# AnalogControlBoard.net
KiCad netlist of a schematic drawn in Altium Designer
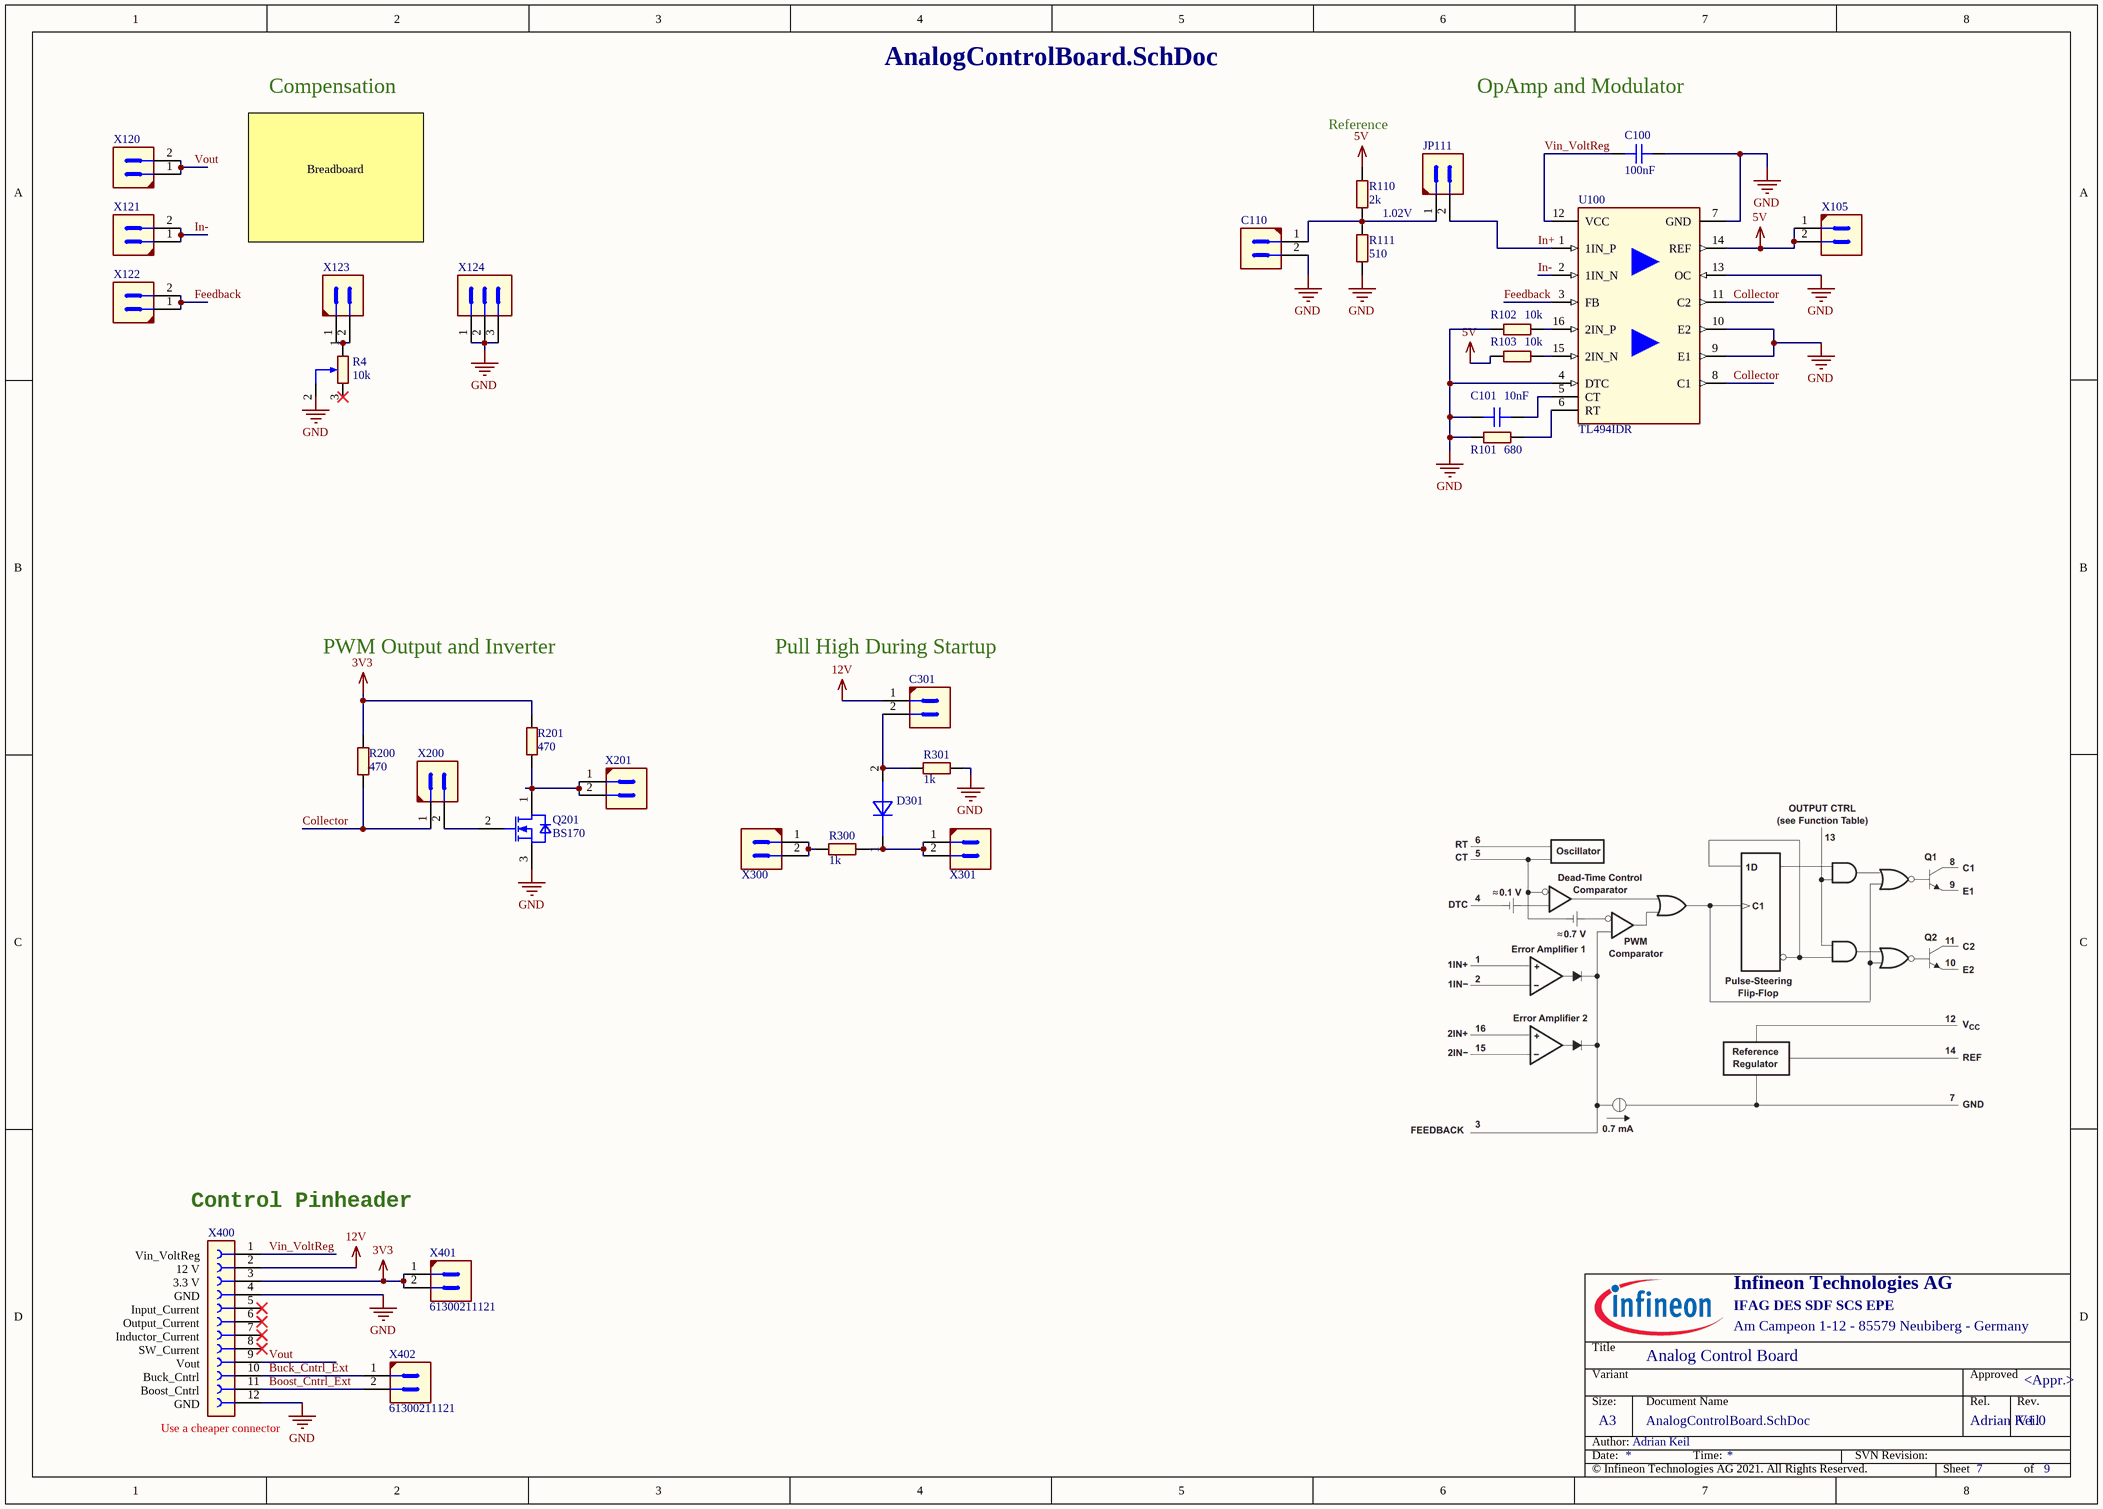
[diagram p0: AnalogControlBoard.SchDoc]

(export (version "E")
  (design (tool "Eeschema 10.0.6"))
  (components
    (comp (ref "C100")
      (value "100nF")
      (footprint "CAPRR254W51L508T318H736B")
      (fields (field (name "LEGACY PARTNUMBER") "CAP01010813") (field (name "MANUFACTURER") "Kemet"))
      (libsource (lib "PCBLibraryData") (part "CAP-SGL-STD-02P_00000001"))
    )
    (comp (ref "C101")
      (value "10nF")
      (footprint "CAPRR254W51L508T318H736B")
      (fields (field (name "LEGACY PARTNUMBER") "CAP01010813") (field (name "MANUFACTURER") "Kemet"))
      (libsource (lib "PCBLibraryData") (part "CAP-SGL-STD-02P_00000001"))
    )
    (comp (ref "C110")
      (value "61300211121")
      (footprint "CON-M-THT-61300211121")
      (description "Header, 2.54mm Pitch, 2 pin, Vertical, Single Row")
      (fields
        (field (name "LEGACY PARTNUMBER") "CON01500943")
        (field (name "MANUFACTURER") "Wurth Elektronik")
      )
      (libsource (lib "") (part "Header 2_3"))
    )
    (comp (ref "C301")
      (value "61300211121")
      (footprint "CON-M-THT-61300211121")
      (description "Header, 2.54mm Pitch, 2 pin, Vertical, Single Row")
      (fields
        (field (name "LEGACY PARTNUMBER") "CON01500943")
        (field (name "MANUFACTURER") "Wurth Elektronik")
      )
      (libsource (lib "") (part "Header 2_1"))
    )
    (comp (ref "D301")
      (value "1N4001-E3/54")
      (footprint "DIOAD1020W78L465D235B")
      (description "General Purpose Plastic Rectifier, 1.0A/50Vrrm")
      (fields (field (name "LEGACY PARTNUMBER") "DIO01300395") (field (name "MANUFACTURER") "Vishay"))
      (libsource (lib "PCBLibraryData") (part "d_std_a"))
    )
    (comp (ref "JP111")
      (value "61300211121")
      (footprint "CON-M-THT-61300211121")
      (description "Header, 2.54mm Pitch, 2 pin, Vertical, Single Row")
      (fields
        (field (name "LEGACY PARTNUMBER") "CON01500943")
        (field (name "MANUFACTURER") "Wurth Elektronik")
      )
      (libsource (lib "") (part "Header 2_2"))
    )
    (comp (ref "Q201")
      (value "BS170")
      (footprint "TO92-THT-2Nxxxx")
      (description "N-Channel, Small Signal MOSFET, 500 mA, 60 Volts")
      (fields
        (field (name "LEGACY PARTNUMBER") "TRA00100106")
        (field (name "MANUFACTURER") "ON Semiconductor")
      )
      (libsource (lib "PCBLibraryData") (part "igfet_n_ch_enh_dio_1d2g3s_3p"))
    )
    (comp (ref "R4")
      (value "10k")
      (footprint "POT-SMD-3361P")
      (fields (field (name "MANUFACTURER") "Bourns"))
      (libsource (lib "PCBLibraryData") (part "RES-SGL-VAR-03P_00000026"))
    )
    (comp (ref "R101")
      (value "680")
      (footprint "RESAD1060W54L680D250B")
      (description "RES / STD / 10k / 250mW / 1% / 50ppm/K / - / 10.60mm C X 0.54mm W 6.80mm L X 2.50mm Dia / - / -")
      (fields (field (name "MANUFACTURER") "Multicomp"))
      (libsource (lib "") (part "RES-SGL-STD-02P_00000006_2"))
    )
    (comp (ref "R102")
      (value "10k")
      (footprint "RESAD1060W54L680D250B")
      (description "RES / STD / 10k / 250mW / 1% / 50ppm/K / - / 10.60mm C X 0.54mm W 6.80mm L X 2.50mm Dia / - / -")
      (fields (field (name "MANUFACTURER") "Multicomp"))
      (libsource (lib "") (part "RES-SGL-STD-02P_00000006_2"))
    )
    (comp (ref "R103")
      (value "10k")
      (footprint "RESAD1060W54L680D250B")
      (description "RES / STD / 10k / 250mW / 1% / 50ppm/K / - / 10.60mm C X 0.54mm W 6.80mm L X 2.50mm Dia / - / -")
      (fields (field (name "MANUFACTURER") "Multicomp"))
      (libsource (lib "") (part "RES-SGL-STD-02P_00000006_2"))
    )
    (comp (ref "R110")
      (value "2k")
      (footprint "RESAD1060W54L680D250B")
      (description "RES / STD / 10k / 250mW / 1% / 50ppm/K / - / 10.60mm C X 0.54mm W 6.80mm L X 2.50mm Dia / - / -")
      (fields (field (name "MANUFACTURER") "Multicomp"))
      (libsource (lib "") (part "RES-SGL-STD-02P_00000006_1"))
    )
    (comp (ref "R111")
      (value "510")
      (footprint "RESAD1060W54L680D250B")
      (description "RES / STD / 10k / 250mW / 1% / 50ppm/K / - / 10.60mm C X 0.54mm W 6.80mm L X 2.50mm Dia / - / -")
      (fields (field (name "MANUFACTURER") "Multicomp"))
      (libsource (lib "") (part "RES-SGL-STD-02P_00000006_1"))
    )
    (comp (ref "R200")
      (value "470")
      (footprint "RESAD1060W54L680D250B")
      (description "RES / STD / 10k / 250mW / 1% / 50ppm/K / - / 10.60mm C X 0.54mm W 6.80mm L X 2.50mm Dia / - / -")
      (fields (field (name "MANUFACTURER") "Multicomp"))
      (libsource (lib "") (part "RES-SGL-STD-02P_00000006_1"))
    )
    (comp (ref "R201")
      (value "470")
      (footprint "RESAD1060W54L680D250B")
      (description "RES / STD / 10k / 250mW / 1% / 50ppm/K / - / 10.60mm C X 0.54mm W 6.80mm L X 2.50mm Dia / - / -")
      (fields (field (name "MANUFACTURER") "Multicomp"))
      (libsource (lib "") (part "RES-SGL-STD-02P_00000006_1"))
    )
    (comp (ref "R300")
      (value "1k")
      (footprint "RESAD1060W54L680D250B")
      (description "RES / STD / 10k / 250mW / 1% / 50ppm/K / - / 10.60mm C X 0.54mm W 6.80mm L X 2.50mm Dia / - / -")
      (fields (field (name "MANUFACTURER") "Multicomp"))
      (libsource (lib "PCBLibraryData") (part "RES-SGL-STD-02P_00000006"))
    )
    (comp (ref "R301")
      (value "1k")
      (footprint "RESAD1060W54L680D250B")
      (description "RES / STD / 10k / 250mW / 1% / 50ppm/K / - / 10.60mm C X 0.54mm W 6.80mm L X 2.50mm Dia / - / -")
      (fields (field (name "MANUFACTURER") "Multicomp"))
      (libsource (lib "PCBLibraryData") (part "RES-SGL-STD-02P_00000006"))
    )
    (comp (ref "U100")
      (value "TL494IDR")
      (footprint "SOIC127P600X175-16N-2-V")
      (fields (field (name "MANUFACTURER") "Texas Instruments"))
      (libsource (lib "PCBLibraryData") (part "TL494xxx"))
    )
    (comp (ref "X105")
      (value "61300211121")
      (footprint "CON-M-THT-61300211121")
      (description "Header, 2.54mm Pitch, 2 pin, Vertical, Single Row")
      (fields
        (field (name "LEGACY PARTNUMBER") "CON01500943")
        (field (name "MANUFACTURER") "Wurth Elektronik")
      )
      (libsource (lib "") (part "Header 2_1"))
    )
    (comp (ref "X120")
      (value "61300211121")
      (footprint "CON-M-THT-61300211121")
      (description "Header, 2.54mm Pitch, 2 pin, Vertical, Single Row")
      (fields
        (field (name "LEGACY PARTNUMBER") "CON01500943")
        (field (name "MANUFACTURER") "Wurth Elektronik")
      )
      (libsource (lib "PCBLibraryData") (part "Header 2"))
    )
    (comp (ref "X121")
      (value "61300211121")
      (footprint "CON-M-THT-61300211121")
      (description "Header, 2.54mm Pitch, 2 pin, Vertical, Single Row")
      (fields
        (field (name "LEGACY PARTNUMBER") "CON01500943")
        (field (name "MANUFACTURER") "Wurth Elektronik")
      )
      (libsource (lib "PCBLibraryData") (part "Header 2"))
    )
    (comp (ref "X122")
      (value "61300211121")
      (footprint "CON-M-THT-61300211121")
      (description "Header, 2.54mm Pitch, 2 pin, Vertical, Single Row")
      (fields
        (field (name "LEGACY PARTNUMBER") "CON01500943")
        (field (name "MANUFACTURER") "Wurth Elektronik")
      )
      (libsource (lib "PCBLibraryData") (part "Header 2"))
    )
    (comp (ref "X123")
      (value "61300211121")
      (footprint "CON-M-THT-61300211121")
      (description "Header, 2.54mm Pitch, 2 pin, Vertical, Single Row")
      (fields
        (field (name "LEGACY PARTNUMBER") "CON01500943")
        (field (name "MANUFACTURER") "Wurth Elektronik")
      )
      (libsource (lib "") (part "Header 2_2"))
    )
    (comp (ref "X124")
      (value "61300311121")
      (footprint "CON-M-THT-61300311121")
      (description "WR-PHD Pin Header")
      (fields (field (name "MANUFACTURER") "Wurth Elektronik"))
      (libsource (lib "PCBLibraryData") (part "Header 3"))
    )
    (comp (ref "X200")
      (value "61300211121")
      (footprint "CON-M-THT-61300211121")
      (description "Header, 2.54mm Pitch, 2 pin, Vertical, Single Row")
      (fields
        (field (name "LEGACY PARTNUMBER") "CON01500943")
        (field (name "MANUFACTURER") "Wurth Elektronik")
      )
      (libsource (lib "") (part "Header 2_2"))
    )
    (comp (ref "X201")
      (value "61300211121")
      (footprint "CON-M-THT-61300211121")
      (description "Header, 2.54mm Pitch, 2 pin, Vertical, Single Row")
      (fields
        (field (name "LEGACY PARTNUMBER") "CON01500943")
        (field (name "MANUFACTURER") "Wurth Elektronik")
      )
      (libsource (lib "") (part "Header 2_1"))
    )
    (comp (ref "X300")
      (value "61300211121")
      (footprint "CON-M-THT-61300211121")
      (description "Header, 2.54mm Pitch, 2 pin, Vertical, Single Row")
      (fields
        (field (name "LEGACY PARTNUMBER") "CON01500943")
        (field (name "MANUFACTURER") "Wurth Elektronik")
      )
      (libsource (lib "") (part "Header 2_3"))
    )
    (comp (ref "X301")
      (value "61300211121")
      (footprint "CON-M-THT-61300211121")
      (description "Header, 2.54mm Pitch, 2 pin, Vertical, Single Row")
      (fields
        (field (name "LEGACY PARTNUMBER") "CON01500943")
        (field (name "MANUFACTURER") "Wurth Elektronik")
      )
      (libsource (lib "") (part "Header 2_1"))
    )
    (comp (ref "X400")
      (value "SSW-112-01-G-S")
      (footprint "CON-F-THT-SSW-112-01-G-S")
      (fields (field (name "MANUFACTURER") "Samtec"))
      (libsource (lib "PCBLibraryData") (part "Socket 12"))
    )
    (comp (ref "X401")
      (value "61300211121")
      (footprint "CON-M-THT-61300211121")
      (description "Header, 2.54mm Pitch, 2 pin, Vertical, Single Row")
      (fields
        (field (name "LEGACY PARTNUMBER") "CON01500943")
        (field (name "MANUFACTURER") "Wurth Elektronik")
      )
      (libsource (lib "") (part "Header 2_1"))
    )
    (comp (ref "X402")
      (value "61300211121")
      (footprint "CON-M-THT-61300211121")
      (description "Header, 2.54mm Pitch, 2 pin, Vertical, Single Row")
      (fields
        (field (name "LEGACY PARTNUMBER") "CON01500943")
        (field (name "MANUFACTURER") "Wurth Elektronik")
      )
      (libsource (lib "") (part "Header 2_1"))
    )
  )
  (nets
    (net (code "1") (name "/Boost_Cntrl_Ext") (class "Default")
      (node (ref "X400") (pin "11") (pinfunction "11_11") (pintype "passive"))
      (node (ref "X402") (pin "2") (pinfunction "2_2") (pintype "passive"))
    )
    (net (code "2") (name "/Buck_Cntrl_Ext") (class "Default")
      (node (ref "X400") (pin "10") (pinfunction "10_10") (pintype "passive"))
      (node (ref "X402") (pin "1") (pinfunction "1_1") (pintype "passive"))
    )
    (net (code "3") (name "/Collector") (class "Default")
      (node (ref "R200") (pin "1") (pinfunction "1_1") (pintype "passive"))
      (node (ref "U100") (pin "11") (pinfunction "C2_11") (pintype "output"))
      (node (ref "U100") (pin "8") (pinfunction "C1_8") (pintype "output"))
      (node (ref "X200") (pin "1") (pinfunction "1_1") (pintype "passive"))
    )
    (net (code "4") (name "/Feedback") (class "Default")
      (node (ref "U100") (pin "3") (pinfunction "FB_3") (pintype "input"))
      (node (ref "X122") (pin "1") (pinfunction "1_1") (pintype "passive"))
      (node (ref "X122") (pin "2") (pinfunction "2_2") (pintype "passive"))
    )
    (net (code "5") (name "/In+") (class "Default")
      (node (ref "JP111") (pin "2") (pinfunction "2_2") (pintype "passive"))
      (node (ref "U100") (pin "1") (pinfunction "1IN_P_1") (pintype "input"))
    )
    (net (code "6") (name "/In-") (class "Default")
      (node (ref "U100") (pin "2") (pinfunction "1IN_N_2") (pintype "input"))
      (node (ref "X121") (pin "1") (pinfunction "1_1") (pintype "passive"))
      (node (ref "X121") (pin "2") (pinfunction "2_2") (pintype "passive"))
    )
    (net (code "7") (name "/Vin_VoltReg") (class "Default")
      (node (ref "C100") (pin "1") (pinfunction "1_1") (pintype "passive"))
      (node (ref "U100") (pin "12") (pinfunction "VCC_12") (pintype "power_in"))
      (node (ref "X400") (pin "1") (pinfunction "1_1") (pintype "passive"))
    )
    (net (code "8") (name "/Vout") (class "Default")
      (node (ref "X120") (pin "1") (pinfunction "1_1") (pintype "passive"))
      (node (ref "X120") (pin "2") (pinfunction "2_2") (pintype "passive"))
      (node (ref "X400") (pin "9") (pinfunction "9_9") (pintype "passive"))
    )
    (net (code "9") (name "3V3") (class "Default")
      (node (ref "R200") (pin "2") (pinfunction "2_2") (pintype "passive"))
      (node (ref "R201") (pin "2") (pinfunction "2_2") (pintype "passive"))
      (node (ref "X400") (pin "3") (pinfunction "3_3") (pintype "passive"))
      (node (ref "X401") (pin "1") (pinfunction "1_1") (pintype "passive"))
      (node (ref "X401") (pin "2") (pinfunction "2_2") (pintype "passive"))
    )
    (net (code "10") (name "5V") (class "Default")
      (node (ref "R103") (pin "1") (pinfunction "1_1") (pintype "passive"))
      (node (ref "R110") (pin "2") (pinfunction "2_2") (pintype "passive"))
      (node (ref "U100") (pin "14") (pinfunction "REF_14") (pintype "output"))
      (node (ref "X105") (pin "1") (pinfunction "1_1") (pintype "passive"))
      (node (ref "X105") (pin "2") (pinfunction "2_2") (pintype "passive"))
    )
    (net (code "11") (name "12V") (class "Default")
      (node (ref "C301") (pin "1") (pinfunction "1_1") (pintype "passive"))
      (node (ref "X400") (pin "2") (pinfunction "2_2") (pintype "passive"))
    )
    (net (code "12") (name "GND") (class "Default")
      (node (ref "C100") (pin "2") (pinfunction "2_2") (pintype "passive"))
      (node (ref "C101") (pin "1") (pinfunction "1_1") (pintype "passive"))
      (node (ref "C110") (pin "2") (pinfunction "2_2") (pintype "passive"))
      (node (ref "Q201") (pin "3") (pinfunction "SOURCE_3") (pintype "passive"))
      (node (ref "R101") (pin "1") (pinfunction "1_1") (pintype "passive"))
      (node (ref "R102") (pin "1") (pinfunction "1_1") (pintype "passive"))
      (node (ref "R111") (pin "1") (pinfunction "1_1") (pintype "passive"))
      (node (ref "R301") (pin "1") (pinfunction "1_1") (pintype "passive"))
      (node (ref "R4") (pin "2") (pinfunction "2_2") (pintype "passive"))
      (node (ref "U100") (pin "10") (pinfunction "E2_10") (pintype "output"))
      (node (ref "U100") (pin "13") (pinfunction "OC_13") (pintype "input"))
      (node (ref "U100") (pin "4") (pinfunction "DTC_4") (pintype "input"))
      (node (ref "U100") (pin "7") (pinfunction "GND_7") (pintype "power_in"))
      (node (ref "U100") (pin "9") (pinfunction "E1_9") (pintype "output"))
      (node (ref "X124") (pin "1") (pinfunction "1_1") (pintype "passive"))
      (node (ref "X124") (pin "2") (pinfunction "2_2") (pintype "passive"))
      (node (ref "X124") (pin "3") (pinfunction "3_3") (pintype "passive"))
      (node (ref "X400") (pin "12") (pinfunction "12_12") (pintype "passive"))
      (node (ref "X400") (pin "4") (pinfunction "4_4") (pintype "passive"))
    )
    (net (code "13") (name "Net-(C110-Pad1)") (class "Default")
      (node (ref "C110") (pin "1") (pinfunction "1_1") (pintype "passive"))
      (node (ref "JP111") (pin "1") (pinfunction "1_1") (pintype "passive"))
      (node (ref "R110") (pin "1") (pinfunction "1_1") (pintype "passive"))
      (node (ref "R111") (pin "2") (pinfunction "2_2") (pintype "passive"))
    )
    (net (code "14") (name "Net-(D301-Anode)") (class "Default")
      (node (ref "C301") (pin "2") (pinfunction "2_2") (pintype "passive"))
      (node (ref "D301") (pin "2") (pinfunction "Anode_2") (pintype "passive"))
      (node (ref "R301") (pin "2") (pinfunction "2_2") (pintype "passive"))
    )
    (net (code "15") (name "Net-(D301-Cathode)") (class "Default")
      (node (ref "D301") (pin "1") (pinfunction "Cathode_1") (pintype "passive"))
      (node (ref "R300") (pin "1") (pinfunction "1_1") (pintype "passive"))
      (node (ref "X301") (pin "1") (pinfunction "1_1") (pintype "passive"))
      (node (ref "X301") (pin "2") (pinfunction "2_2") (pintype "passive"))
    )
    (net (code "16") (name "Net-(Q201-DRAIN)") (class "Default")
      (node (ref "Q201") (pin "1") (pinfunction "DRAIN_1") (pintype "passive"))
      (node (ref "R201") (pin "1") (pinfunction "1_1") (pintype "passive"))
      (node (ref "X201") (pin "1") (pinfunction "1_1") (pintype "passive"))
      (node (ref "X201") (pin "2") (pinfunction "2_2") (pintype "passive"))
    )
    (net (code "17") (name "Net-(Q201-GATE)") (class "Default")
      (node (ref "Q201") (pin "2") (pinfunction "GATE_2") (pintype "passive"))
      (node (ref "X200") (pin "2") (pinfunction "2_2") (pintype "passive"))
    )
    (net (code "18") (name "Net-(R4-Pad1)") (class "Default")
      (node (ref "R4") (pin "1") (pinfunction "1_1") (pintype "passive"))
      (node (ref "X123") (pin "1") (pinfunction "1_1") (pintype "passive"))
      (node (ref "X123") (pin "2") (pinfunction "2_2") (pintype "passive"))
    )
    (net (code "19") (name "Net-(R300-Pad2)") (class "Default")
      (node (ref "R300") (pin "2") (pinfunction "2_2") (pintype "passive"))
      (node (ref "X300") (pin "1") (pinfunction "1_1") (pintype "passive"))
      (node (ref "X300") (pin "2") (pinfunction "2_2") (pintype "passive"))
    )
    (net (code "20") (name "Net-(U100-2IN_N)") (class "Default")
      (node (ref "R103") (pin "2") (pinfunction "2_2") (pintype "passive"))
      (node (ref "U100") (pin "15") (pinfunction "2IN_N_15") (pintype "input"))
    )
    (net (code "21") (name "Net-(U100-2IN_P)") (class "Default")
      (node (ref "R102") (pin "2") (pinfunction "2_2") (pintype "passive"))
      (node (ref "U100") (pin "16") (pinfunction "2IN_P_16") (pintype "input"))
    )
    (net (code "22") (name "Net-(U100-CT)") (class "Default")
      (node (ref "C101") (pin "2") (pinfunction "2_2") (pintype "passive"))
      (node (ref "U100") (pin "5") (pinfunction "CT_5") (pintype "passive"))
    )
    (net (code "23") (name "Net-(U100-RT)") (class "Default")
      (node (ref "R101") (pin "2") (pinfunction "2_2") (pintype "passive"))
      (node (ref "U100") (pin "6") (pinfunction "RT_6") (pintype "passive"))
    )
    (net (code "24") (name "unconnected-(R4-Pad3)") (class "Default")
      (node (ref "R4") (pin "3") (pinfunction "3_3") (pintype "passive+no_connect"))
    )
    (net (code "25") (name "unconnected-(X400-Pad5)") (class "Default")
      (node (ref "X400") (pin "5") (pinfunction "5_5") (pintype "passive+no_connect"))
    )
    (net (code "26") (name "unconnected-(X400-Pad6)") (class "Default")
      (node (ref "X400") (pin "6") (pinfunction "6_6") (pintype "passive+no_connect"))
    )
    (net (code "27") (name "unconnected-(X400-Pad7)") (class "Default")
      (node (ref "X400") (pin "7") (pinfunction "7_7") (pintype "passive+no_connect"))
    )
    (net (code "28") (name "unconnected-(X400-Pad8)") (class "Default")
      (node (ref "X400") (pin "8") (pinfunction "8_8") (pintype "passive+no_connect"))
    )
  )
)
